# DC_DC_12V.net
KiCad netlist of a schematic drawn in Altium Designer
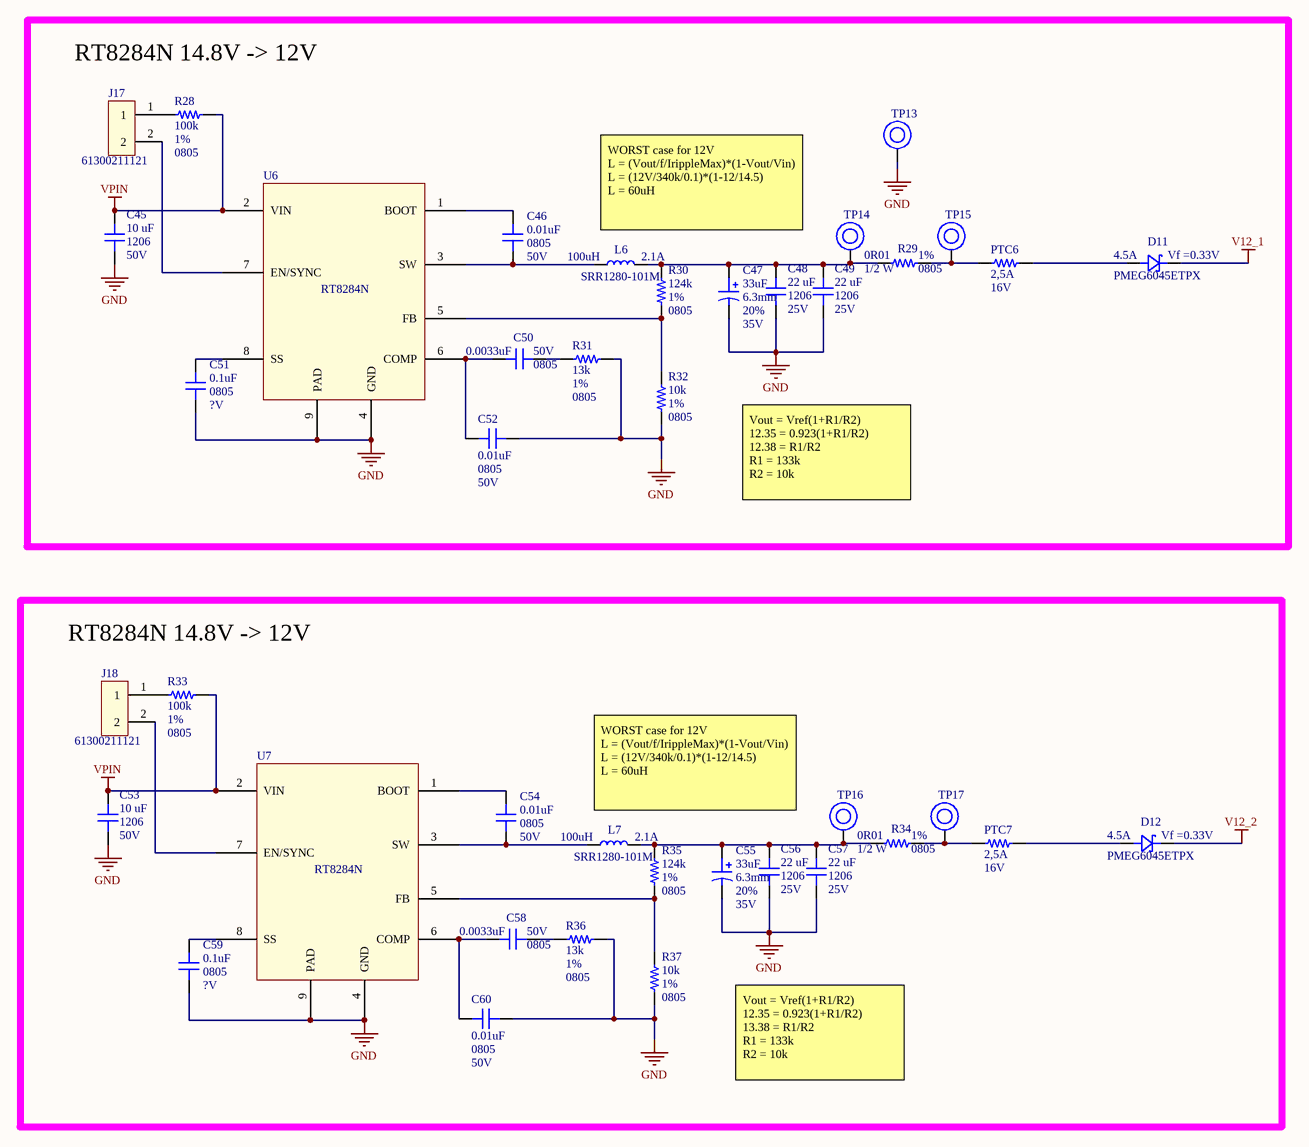
[diagram p0: DC_DC_12V.SchDoc]

(export (version "E")
  (design (tool "Eeschema 10.0.6"))
  (components
    (comp (ref "C45")
      (value "10 uF")
      (footprint "CAP_1206")
      (description "CAP - 1206")
      (fields
        (field (name "PACKAGE") "1206")
        (field (name "VOLTAGE") "50V")
        (field (name "PART NUMBER") "GRT31CR61H106ME01L")
      )
      (libsource (lib "SecureBot") (part "CAP - 1206"))
    )
    (comp (ref "C46")
      (value "0.01uF")
      (footprint "CAP_0805")
      (description "CAP - 0805")
      (fields
        (field (name "PART NUMBER") "CL21B103KBANNNC")
        (field (name "PACKAGE") "0805")
        (field (name "VOLTAGE") "50V")
      )
      (libsource (lib "SecureBot") (part "CAP - 0805"))
    )
    (comp (ref "C47")
      (value "33uF")
      (footprint "CAP ALU - 6.3mm DIA")
      (description "CAP ALU - 6.3mm")
      (fields
        (field (name "PACKAGE") "6.3mm")
        (field (name "TOLERANCE") "20%")
        (field (name "VOLTAGE") "35V")
        (field (name "PART NUMBER") "EEE-FK1V330P")
      )
      (libsource (lib "SecureBot") (part "CAP ALU - 6_3mm"))
    )
    (comp (ref "C48")
      (value "22 uF")
      (footprint "CAP_1206")
      (description "CAP - 1206")
      (fields
        (field (name "PACKAGE") "1206")
        (field (name "VOLTAGE") "25V")
        (field (name "PART NUMBER") "CL31A226KAHNNNE")
      )
      (libsource (lib "SecureBot") (part "CAP - 1206"))
    )
    (comp (ref "C49")
      (value "22 uF")
      (footprint "CAP_1206")
      (description "CAP - 1206")
      (fields
        (field (name "PACKAGE") "1206")
        (field (name "VOLTAGE") "25V")
        (field (name "PART NUMBER") "CL31A226KAHNNNE")
      )
      (libsource (lib "SecureBot") (part "CAP - 1206"))
    )
    (comp (ref "C50")
      (value "0.0033uF")
      (footprint "CAP_0805")
      (description "CAP - 0805")
      (fields
        (field (name "PART NUMBER") "CL21B332KBANNNC")
        (field (name "PACKAGE") "0805")
        (field (name "VOLTAGE") "50V")
      )
      (libsource (lib "SecureBot") (part "CAP - 0805"))
    )
    (comp (ref "C51")
      (value "0.1uF")
      (footprint "CAP_0805")
      (description "CAP - 0805")
      (fields
        (field (name "PART NUMBER") "CC0805KRX7R9BB104")
        (field (name "PACKAGE") "0805")
        (field (name "VOLTAGE") "?V")
      )
      (libsource (lib "SecureBot") (part "CAP - 0805"))
    )
    (comp (ref "C52")
      (value "0.01uF")
      (footprint "CAP_0805")
      (description "CAP - 0805")
      (fields
        (field (name "PART NUMBER") "CL21B103KBANNNC")
        (field (name "PACKAGE") "0805")
        (field (name "VOLTAGE") "50V")
      )
      (libsource (lib "SecureBot") (part "CAP - 0805"))
    )
    (comp (ref "C53")
      (value "10 uF")
      (footprint "CAP_1206")
      (description "CAP - 1206")
      (fields
        (field (name "PACKAGE") "1206")
        (field (name "VOLTAGE") "50V")
        (field (name "PART NUMBER") "GRT31CR61H106ME01L")
      )
      (libsource (lib "SecureBot") (part "CAP - 1206"))
    )
    (comp (ref "C54")
      (value "0.01uF")
      (footprint "CAP_0805")
      (description "CAP - 0805")
      (fields
        (field (name "PART NUMBER") "CL21B103KBANNNC")
        (field (name "PACKAGE") "0805")
        (field (name "VOLTAGE") "50V")
      )
      (libsource (lib "SecureBot") (part "CAP - 0805"))
    )
    (comp (ref "C55")
      (value "33uF")
      (footprint "CAP ALU - 6.3mm DIA")
      (description "CAP ALU - 6.3mm")
      (fields
        (field (name "PACKAGE") "6.3mm")
        (field (name "TOLERANCE") "20%")
        (field (name "VOLTAGE") "35V")
        (field (name "PART NUMBER") "EEE-FK1V330P")
      )
      (libsource (lib "SecureBot") (part "CAP ALU - 6_3mm"))
    )
    (comp (ref "C56")
      (value "22 uF")
      (footprint "CAP_1206")
      (description "CAP - 1206")
      (fields
        (field (name "PACKAGE") "1206")
        (field (name "VOLTAGE") "25V")
        (field (name "PART NUMBER") "CL31A226KAHNNNE")
      )
      (libsource (lib "SecureBot") (part "CAP - 1206"))
    )
    (comp (ref "C57")
      (value "22 uF")
      (footprint "CAP_1206")
      (description "CAP - 1206")
      (fields
        (field (name "PACKAGE") "1206")
        (field (name "VOLTAGE") "25V")
        (field (name "PART NUMBER") "CL31A226KAHNNNE")
      )
      (libsource (lib "SecureBot") (part "CAP - 1206"))
    )
    (comp (ref "C58")
      (value "0.0033uF")
      (footprint "CAP_0805")
      (description "CAP - 0805")
      (fields
        (field (name "PART NUMBER") "CL21B332KBANNNC")
        (field (name "PACKAGE") "0805")
        (field (name "VOLTAGE") "50V")
      )
      (libsource (lib "SecureBot") (part "CAP - 0805"))
    )
    (comp (ref "C59")
      (value "0.1uF")
      (footprint "CAP_0805")
      (description "CAP - 0805")
      (fields
        (field (name "PART NUMBER") "CC0805KRX7R9BB104")
        (field (name "PACKAGE") "0805")
        (field (name "VOLTAGE") "?V")
      )
      (libsource (lib "SecureBot") (part "CAP - 0805"))
    )
    (comp (ref "C60")
      (value "0.01uF")
      (footprint "CAP_0805")
      (description "CAP - 0805")
      (fields
        (field (name "PART NUMBER") "CL21B103KBANNNC")
        (field (name "PACKAGE") "0805")
        (field (name "VOLTAGE") "50V")
      )
      (libsource (lib "SecureBot") (part "CAP - 0805"))
    )
    (comp (ref "D11")
      (value "SCHOTTKEY")
      (footprint "DO-214AC_SOD128")
      (fields
        (field (name "CURRENT") "4.5A")
        (field (name "VF") "Vf =0.33V")
        (field (name "PART NUMBER") "PMEG6045ETPX")
      )
      (libsource (lib "SecureBot") (part "SCHOTTKEY"))
    )
    (comp (ref "D12")
      (value "SCHOTTKEY")
      (footprint "DO-214AC_SOD128")
      (fields
        (field (name "CURRENT") "4.5A")
        (field (name "VF") "Vf =0.33V")
        (field (name "PART NUMBER") "PMEG6045ETPX")
      )
      (libsource (lib "SecureBot") (part "SCHOTTKEY"))
    )
    (comp (ref "J17")
      (value "Header 2 pin SM")
      (footprint "HDR1X2")
      (fields (field (name "PART NUMBER") "61300211121"))
      (libsource (lib "SecureBot") (part "Header 2 pin SM"))
    )
    (comp (ref "J18")
      (value "Header 2 pin SM")
      (footprint "HDR1X2")
      (fields (field (name "PART NUMBER") "61300211121"))
      (libsource (lib "SecureBot") (part "Header 2 pin SM"))
    )
    (comp (ref "L6")
      (value "100uH")
      (footprint "BOURNS 12.5x12.5mm")
      (description "IND")
      (fields (field (name "CURRENT") "2.1A") (field (name "PART NUMBER") "SRR1280-101M"))
      (libsource (lib "SecureBot") (part "IND"))
    )
    (comp (ref "L7")
      (value "100uH")
      (footprint "BOURNS 12.5x12.5mm")
      (description "IND")
      (fields (field (name "CURRENT") "2.1A") (field (name "PART NUMBER") "SRR1280-101M"))
      (libsource (lib "SecureBot") (part "IND"))
    )
    (comp (ref "PTC6")
      (value "PTC - 1812")
      (footprint "PTC - 1812")
      (fields
        (field (name "PART NUMBER") "0ZCG0160BF2C")
        (field (name "TRIP VALUE") "2,5A")
        (field (name "VOLTAGE") "16V")
      )
      (libsource (lib "SecureBot") (part "PTC - 1812"))
    )
    (comp (ref "PTC7")
      (value "PTC - 1812")
      (footprint "PTC - 1812")
      (fields
        (field (name "PART NUMBER") "0ZCG0160BF2C")
        (field (name "TRIP VALUE") "2,5A")
        (field (name "VOLTAGE") "16V")
      )
      (libsource (lib "SecureBot") (part "PTC - 1812"))
    )
    (comp (ref "R28")
      (value "100k")
      (footprint "FER_0805")
      (description "RES - 0805")
      (fields
        (field (name "TOLERANCE") "1%")
        (field (name "PACKAGE") "0805")
        (field (name "PART NUMBER") "RMCF0805FT100K")
      )
      (libsource (lib "SecureBot") (part "RES - 0805"))
    )
    (comp (ref "R29")
      (value "0R01")
      (footprint "FER_0805")
      (description "RES - 0805")
      (fields
        (field (name "WATT") "1/2 W")
        (field (name "TOLERANCE") "1%")
        (field (name "PACKAGE") "0805")
        (field (name "PART NUMBER") "KRL1220E-M-R010-F-T5")
      )
      (libsource (lib "SecureBot") (part "RES - 0805"))
    )
    (comp (ref "R30")
      (value "124k")
      (footprint "FER_0805")
      (description "RES - 0805")
      (fields
        (field (name "TOLERANCE") "1%")
        (field (name "PACKAGE") "0805")
        (field (name "PART NUMBER") "RMCF0805FT124K")
      )
      (libsource (lib "SecureBot") (part "RES - 0805"))
    )
    (comp (ref "R31")
      (value "13k")
      (footprint "FER_0805")
      (description "RES - 0805")
      (fields
        (field (name "TOLERANCE") "1%")
        (field (name "PACKAGE") "0805")
        (field (name "PART NUMBER") "RC0805FR-0713KL")
      )
      (libsource (lib "SecureBot") (part "RES - 0805"))
    )
    (comp (ref "R32")
      (value "10k")
      (footprint "FER_0805")
      (description "RES - 0805")
      (fields
        (field (name "TOLERANCE") "1%")
        (field (name "PACKAGE") "0805")
        (field (name "PART NUMBER") "RMCF0805FT10K0")
      )
      (libsource (lib "SecureBot") (part "RES - 0805"))
    )
    (comp (ref "R33")
      (value "100k")
      (footprint "FER_0805")
      (description "RES - 0805")
      (fields
        (field (name "TOLERANCE") "1%")
        (field (name "PACKAGE") "0805")
        (field (name "PART NUMBER") "RMCF0805FT100K")
      )
      (libsource (lib "SecureBot") (part "RES - 0805"))
    )
    (comp (ref "R34")
      (value "0R01")
      (footprint "FER_0805")
      (description "RES - 0805")
      (fields
        (field (name "WATT") "1/2 W")
        (field (name "TOLERANCE") "1%")
        (field (name "PACKAGE") "0805")
        (field (name "PART NUMBER") "KRL1220E-M-R010-F-T5")
      )
      (libsource (lib "SecureBot") (part "RES - 0805"))
    )
    (comp (ref "R35")
      (value "124k")
      (footprint "FER_0805")
      (description "RES - 0805")
      (fields
        (field (name "TOLERANCE") "1%")
        (field (name "PACKAGE") "0805")
        (field (name "PART NUMBER") "RMCF0805FT124K")
      )
      (libsource (lib "SecureBot") (part "RES - 0805"))
    )
    (comp (ref "R36")
      (value "13k")
      (footprint "FER_0805")
      (description "RES - 0805")
      (fields
        (field (name "TOLERANCE") "1%")
        (field (name "PACKAGE") "0805")
        (field (name "PART NUMBER") "RC0805FR-0713KL")
      )
      (libsource (lib "SecureBot") (part "RES - 0805"))
    )
    (comp (ref "R37")
      (value "10k")
      (footprint "FER_0805")
      (description "RES - 0805")
      (fields
        (field (name "TOLERANCE") "1%")
        (field (name "PACKAGE") "0805")
        (field (name "PART NUMBER") "RMCF0805FT10K0")
      )
      (libsource (lib "SecureBot") (part "RES - 0805"))
    )
    (comp (ref "TP13")
      (value "TestPoint 3x3mm")
      (footprint "TestPoint 3X3mm")
      (libsource (lib "SecureBot") (part "TestPoint 3x3mm"))
    )
    (comp (ref "TP14")
      (value "TestPoint 3x3mm")
      (footprint "TestPoint 3X3mm")
      (libsource (lib "SecureBot") (part "TestPoint 3x3mm"))
    )
    (comp (ref "TP15")
      (value "TestPoint 3x3mm")
      (footprint "TestPoint 3X3mm")
      (libsource (lib "SecureBot") (part "TestPoint 3x3mm"))
    )
    (comp (ref "TP16")
      (value "TestPoint 3x3mm")
      (footprint "TestPoint 3X3mm")
      (libsource (lib "SecureBot") (part "TestPoint 3x3mm"))
    )
    (comp (ref "TP17")
      (value "TestPoint 3x3mm")
      (footprint "TestPoint 3X3mm")
      (libsource (lib "SecureBot") (part "TestPoint 3x3mm"))
    )
    (comp (ref "U6") (value "RT8284N") (footprint "SOP8") (libsource (lib "SecureBot") (part "RT8284N")))
    (comp (ref "U7") (value "RT8284N") (footprint "SOP8") (libsource (lib "SecureBot") (part "RT8284N")))
  )
  (nets
    (net (code "1") (name "GND") (class "Default")
      (node (ref "C45") (pin "2") (pinfunction "2_2") (pintype "passive"))
      (node (ref "C47") (pin "2") (pinfunction "2_2") (pintype "passive"))
      (node (ref "C48") (pin "2") (pinfunction "2_2") (pintype "passive"))
      (node (ref "C49") (pin "2") (pinfunction "2_2") (pintype "passive"))
      (node (ref "C51") (pin "2") (pinfunction "2_2") (pintype "passive"))
      (node (ref "C52") (pin "2") (pinfunction "2_2") (pintype "passive"))
      (node (ref "C53") (pin "2") (pinfunction "2_2") (pintype "passive"))
      (node (ref "C55") (pin "2") (pinfunction "2_2") (pintype "passive"))
      (node (ref "C56") (pin "2") (pinfunction "2_2") (pintype "passive"))
      (node (ref "C57") (pin "2") (pinfunction "2_2") (pintype "passive"))
      (node (ref "C59") (pin "2") (pinfunction "2_2") (pintype "passive"))
      (node (ref "C60") (pin "2") (pinfunction "2_2") (pintype "passive"))
      (node (ref "R31") (pin "2") (pinfunction "2_2") (pintype "passive"))
      (node (ref "R32") (pin "2") (pinfunction "2_2") (pintype "passive"))
      (node (ref "R36") (pin "2") (pinfunction "2_2") (pintype "passive"))
      (node (ref "R37") (pin "2") (pinfunction "2_2") (pintype "passive"))
      (node (ref "TP13") (pin "1") (pinfunction "1_1") (pintype "passive"))
      (node (ref "U6") (pin "4") (pinfunction "GND_4") (pintype "passive"))
      (node (ref "U6") (pin "9") (pinfunction "PAD_9") (pintype "passive"))
      (node (ref "U7") (pin "4") (pinfunction "GND_4") (pintype "passive"))
      (node (ref "U7") (pin "9") (pinfunction "PAD_9") (pintype "passive"))
    )
    (net (code "2") (name "Net-(C47-Pad1)") (class "Default")
      (node (ref "C47") (pin "1") (pinfunction "1_1") (pintype "passive"))
      (node (ref "C48") (pin "1") (pinfunction "1_1") (pintype "passive"))
      (node (ref "C49") (pin "1") (pinfunction "1_1") (pintype "passive"))
      (node (ref "L6") (pin "2") (pinfunction "2_2") (pintype "passive"))
      (node (ref "R29") (pin "1") (pinfunction "1_1") (pintype "passive"))
      (node (ref "R30") (pin "1") (pinfunction "1_1") (pintype "passive"))
      (node (ref "TP14") (pin "1") (pinfunction "1_1") (pintype "passive"))
    )
    (net (code "3") (name "Net-(C50-Pad2)") (class "Default")
      (node (ref "C50") (pin "2") (pinfunction "2_2") (pintype "passive"))
      (node (ref "R31") (pin "1") (pinfunction "1_1") (pintype "passive"))
    )
    (net (code "4") (name "Net-(C55-Pad1)") (class "Default")
      (node (ref "C55") (pin "1") (pinfunction "1_1") (pintype "passive"))
      (node (ref "C56") (pin "1") (pinfunction "1_1") (pintype "passive"))
      (node (ref "C57") (pin "1") (pinfunction "1_1") (pintype "passive"))
      (node (ref "L7") (pin "2") (pinfunction "2_2") (pintype "passive"))
      (node (ref "R34") (pin "1") (pinfunction "1_1") (pintype "passive"))
      (node (ref "R35") (pin "1") (pinfunction "1_1") (pintype "passive"))
      (node (ref "TP16") (pin "1") (pinfunction "1_1") (pintype "passive"))
    )
    (net (code "5") (name "Net-(C58-Pad2)") (class "Default")
      (node (ref "C58") (pin "2") (pinfunction "2_2") (pintype "passive"))
      (node (ref "R36") (pin "1") (pinfunction "1_1") (pintype "passive"))
    )
    (net (code "6") (name "Net-(D11-Pad1)") (class "Default")
      (node (ref "D11") (pin "1") (pinfunction "1_1") (pintype "passive"))
      (node (ref "PTC6") (pin "2") (pinfunction "2_2") (pintype "passive"))
    )
    (net (code "7") (name "Net-(D12-Pad1)") (class "Default")
      (node (ref "D12") (pin "1") (pinfunction "1_1") (pintype "passive"))
      (node (ref "PTC7") (pin "2") (pinfunction "2_2") (pintype "passive"))
    )
    (net (code "8") (name "Net-(J17-Pad1)") (class "Default")
      (node (ref "J17") (pin "1") (pinfunction "1_1") (pintype "passive"))
      (node (ref "R28") (pin "1") (pinfunction "1_1") (pintype "passive"))
    )
    (net (code "9") (name "Net-(J18-Pad1)") (class "Default")
      (node (ref "J18") (pin "1") (pinfunction "1_1") (pintype "passive"))
      (node (ref "R33") (pin "1") (pinfunction "1_1") (pintype "passive"))
    )
    (net (code "10") (name "Net-(PTC6-Pad1)") (class "Default")
      (node (ref "PTC6") (pin "1") (pinfunction "1_1") (pintype "passive"))
      (node (ref "R29") (pin "2") (pinfunction "2_2") (pintype "passive"))
      (node (ref "TP15") (pin "1") (pinfunction "1_1") (pintype "passive"))
    )
    (net (code "11") (name "Net-(PTC7-Pad1)") (class "Default")
      (node (ref "PTC7") (pin "1") (pinfunction "1_1") (pintype "passive"))
      (node (ref "R34") (pin "2") (pinfunction "2_2") (pintype "passive"))
      (node (ref "TP17") (pin "1") (pinfunction "1_1") (pintype "passive"))
    )
    (net (code "12") (name "Net-(U6-BOOT)") (class "Default")
      (node (ref "C46") (pin "1") (pinfunction "1_1") (pintype "passive"))
      (node (ref "U6") (pin "1") (pinfunction "BOOT_1") (pintype "passive"))
    )
    (net (code "13") (name "Net-(U6-COMP)") (class "Default")
      (node (ref "C50") (pin "1") (pinfunction "1_1") (pintype "passive"))
      (node (ref "C52") (pin "1") (pinfunction "1_1") (pintype "passive"))
      (node (ref "U6") (pin "6") (pinfunction "COMP_6") (pintype "passive"))
    )
    (net (code "14") (name "Net-(U6-EN{slash}SYNC)") (class "Default")
      (node (ref "J17") (pin "2") (pinfunction "2_2") (pintype "passive"))
      (node (ref "U6") (pin "7") (pinfunction "EN/SYNC_7") (pintype "passive"))
    )
    (net (code "15") (name "Net-(U6-FB)") (class "Default")
      (node (ref "R30") (pin "2") (pinfunction "2_2") (pintype "passive"))
      (node (ref "R32") (pin "1") (pinfunction "1_1") (pintype "passive"))
      (node (ref "U6") (pin "5") (pinfunction "FB_5") (pintype "passive"))
    )
    (net (code "16") (name "Net-(U6-SS)") (class "Default")
      (node (ref "C51") (pin "1") (pinfunction "1_1") (pintype "passive"))
      (node (ref "U6") (pin "8") (pinfunction "SS_8") (pintype "passive"))
    )
    (net (code "17") (name "Net-(U6-SW)") (class "Default")
      (node (ref "C46") (pin "2") (pinfunction "2_2") (pintype "passive"))
      (node (ref "L6") (pin "1") (pinfunction "1_1") (pintype "passive"))
      (node (ref "U6") (pin "3") (pinfunction "SW_3") (pintype "passive"))
    )
    (net (code "18") (name "Net-(U7-BOOT)") (class "Default")
      (node (ref "C54") (pin "1") (pinfunction "1_1") (pintype "passive"))
      (node (ref "U7") (pin "1") (pinfunction "BOOT_1") (pintype "passive"))
    )
    (net (code "19") (name "Net-(U7-COMP)") (class "Default")
      (node (ref "C58") (pin "1") (pinfunction "1_1") (pintype "passive"))
      (node (ref "C60") (pin "1") (pinfunction "1_1") (pintype "passive"))
      (node (ref "U7") (pin "6") (pinfunction "COMP_6") (pintype "passive"))
    )
    (net (code "20") (name "Net-(U7-EN{slash}SYNC)") (class "Default")
      (node (ref "J18") (pin "2") (pinfunction "2_2") (pintype "passive"))
      (node (ref "U7") (pin "7") (pinfunction "EN/SYNC_7") (pintype "passive"))
    )
    (net (code "21") (name "Net-(U7-FB)") (class "Default")
      (node (ref "R35") (pin "2") (pinfunction "2_2") (pintype "passive"))
      (node (ref "R37") (pin "1") (pinfunction "1_1") (pintype "passive"))
      (node (ref "U7") (pin "5") (pinfunction "FB_5") (pintype "passive"))
    )
    (net (code "22") (name "Net-(U7-SS)") (class "Default")
      (node (ref "C59") (pin "1") (pinfunction "1_1") (pintype "passive"))
      (node (ref "U7") (pin "8") (pinfunction "SS_8") (pintype "passive"))
    )
    (net (code "23") (name "Net-(U7-SW)") (class "Default")
      (node (ref "C54") (pin "2") (pinfunction "2_2") (pintype "passive"))
      (node (ref "L7") (pin "1") (pinfunction "1_1") (pintype "passive"))
      (node (ref "U7") (pin "3") (pinfunction "SW_3") (pintype "passive"))
    )
    (net (code "24") (name "V12_1") (class "Default")
      (node (ref "D11") (pin "2") (pinfunction "2_2") (pintype "passive"))
    )
    (net (code "25") (name "V12_2") (class "Default")
      (node (ref "D12") (pin "2") (pinfunction "2_2") (pintype "passive"))
    )
    (net (code "26") (name "VPIN") (class "Default")
      (node (ref "C45") (pin "1") (pinfunction "1_1") (pintype "passive"))
      (node (ref "C53") (pin "1") (pinfunction "1_1") (pintype "passive"))
      (node (ref "R28") (pin "2") (pinfunction "2_2") (pintype "passive"))
      (node (ref "R33") (pin "2") (pinfunction "2_2") (pintype "passive"))
      (node (ref "U6") (pin "2") (pinfunction "VIN_2") (pintype "passive"))
      (node (ref "U7") (pin "2") (pinfunction "VIN_2") (pintype "passive"))
    )
  )
)
